# deska.net
KiCad netlist of a schematic drawn in EAGLE
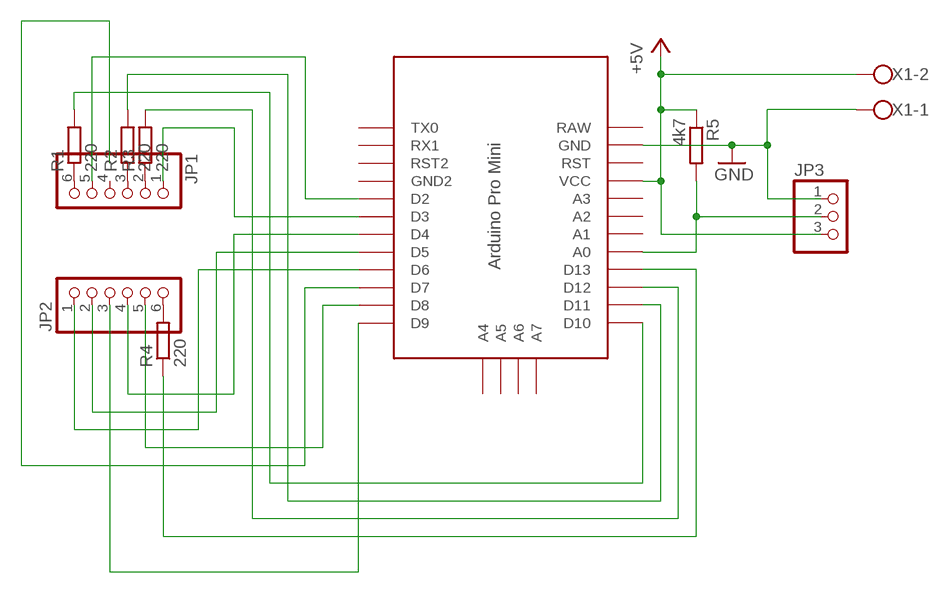
[diagram p0: schematic, sheet 1]

(export (version "E")
  (design (tool "Eeschema 10.0.6"))
  (components
    (comp (ref "JP1")
      (value "PINHD-1X6")
      (footprint "eagle-import:1X06")
      (libsource (lib "eagle-import") (part "PINHD-1X6"))
    )
    (comp (ref "JP2")
      (value "PINHD-1X6")
      (footprint "eagle-import:1X06")
      (libsource (lib "eagle-import") (part "PINHD-1X6"))
    )
    (comp (ref "JP3")
      (value "PINHD-1X3")
      (footprint "eagle-import:1X03")
      (libsource (lib "eagle-import") (part "PINHD-1X3"))
    )
    (comp (ref "R1")
      (value "220")
      (footprint "eagle-import:0204_7")
      (libsource (lib "eagle-import") (part "R-EU_0204/7"))
    )
    (comp (ref "R2")
      (value "220")
      (footprint "eagle-import:0204_7")
      (libsource (lib "eagle-import") (part "R-EU_0204/7"))
    )
    (comp (ref "R3")
      (value "220")
      (footprint "eagle-import:0204_7")
      (libsource (lib "eagle-import") (part "R-EU_0204/7"))
    )
    (comp (ref "R4")
      (value "220")
      (footprint "eagle-import:0204_7")
      (libsource (lib "eagle-import") (part "R-EU_0204/7"))
    )
    (comp (ref "R5")
      (value "4k7")
      (footprint "eagle-import:0204_7")
      (libsource (lib "eagle-import") (part "R-EU_0204/7"))
    )
    (comp (ref "U$1")
      (value "PRO-MINI")
      (footprint "eagle-import:PRO-MINI")
      (libsource (lib "eagle-import") (part "PRO-MINI"))
    )
    (comp (ref "X1")
      (value "W237-102")
      (footprint "eagle-import:W237-102")
      (fields (field (name "MPN") "237-102"))
      (libsource (lib "eagle-import") (part "W237-102"))
    )
  )
  (nets
    (net (code "1") (name "+5V") (class "Default")
      (node (ref "JP3") (pin "3") (pinfunction "3_3") (pintype "passive"))
      (node (ref "R5") (pin "1") (pinfunction "1_1") (pintype "passive"))
      (node (ref "U$1") (pin "VCC") (pinfunction "VCC_VCC") (pintype "bidirectional"))
      (node (ref "X1") (pin "2") (pinfunction "KL_2") (pintype "passive"))
    )
    (net (code "2") (name "/RAW") (class "Default")
      (node (ref "U$1") (pin "RAW") (pinfunction "RAW_RAW") (pintype "power_in"))
    )
    (net (code "3") (name "GND") (class "Default")
      (node (ref "JP3") (pin "1") (pinfunction "1_1") (pintype "passive"))
      (node (ref "U$1") (pin "GND") (pinfunction "GND_GND") (pintype "input"))
      (node (ref "X1") (pin "1") (pinfunction "KL_1") (pintype "passive"))
    )
    (net (code "4") (name "Net-(JP1-Pad1)") (class "Default")
      (node (ref "JP1") (pin "1") (pinfunction "1_1") (pintype "passive"))
      (node (ref "U$1") (pin "D3") (pinfunction "D3_D3") (pintype "bidirectional"))
    )
    (net (code "5") (name "Net-(JP1-Pad2)") (class "Default")
      (node (ref "JP1") (pin "2") (pinfunction "2_2") (pintype "passive"))
      (node (ref "R3") (pin "1") (pinfunction "1_1") (pintype "passive"))
    )
    (net (code "6") (name "Net-(JP1-Pad3)") (class "Default")
      (node (ref "JP1") (pin "3") (pinfunction "3_3") (pintype "passive"))
      (node (ref "R2") (pin "1") (pinfunction "1_1") (pintype "passive"))
    )
    (net (code "7") (name "Net-(JP1-Pad5)") (class "Default")
      (node (ref "JP1") (pin "5") (pinfunction "5_5") (pintype "passive"))
      (node (ref "U$1") (pin "D2") (pinfunction "D2_D2") (pintype "bidirectional"))
    )
    (net (code "8") (name "Net-(JP1-Pad6)") (class "Default")
      (node (ref "JP1") (pin "6") (pinfunction "6_6") (pintype "passive"))
      (node (ref "R1") (pin "1") (pinfunction "1_1") (pintype "passive"))
    )
    (net (code "9") (name "Net-(JP2-Pad1)") (class "Default")
      (node (ref "JP2") (pin "1") (pinfunction "1_1") (pintype "passive"))
      (node (ref "U$1") (pin "D6") (pinfunction "D6_D6") (pintype "bidirectional"))
    )
    (net (code "10") (name "Net-(JP2-Pad2)") (class "Default")
      (node (ref "JP2") (pin "2") (pinfunction "2_2") (pintype "passive"))
      (node (ref "U$1") (pin "D5") (pinfunction "D5_D5") (pintype "bidirectional"))
    )
    (net (code "11") (name "Net-(JP2-Pad3)") (class "Default")
      (node (ref "JP2") (pin "3") (pinfunction "3_3") (pintype "passive"))
      (node (ref "U$1") (pin "D9") (pinfunction "D9_D9") (pintype "bidirectional"))
    )
    (net (code "12") (name "Net-(JP2-Pad4)") (class "Default")
      (node (ref "JP2") (pin "4") (pinfunction "4_4") (pintype "passive"))
      (node (ref "U$1") (pin "D4") (pinfunction "D4_D4") (pintype "bidirectional"))
    )
    (net (code "13") (name "Net-(JP2-Pad5)") (class "Default")
      (node (ref "JP2") (pin "5") (pinfunction "5_5") (pintype "passive"))
      (node (ref "U$1") (pin "D8") (pinfunction "D8_D8") (pintype "bidirectional"))
    )
    (net (code "14") (name "Net-(JP2-Pad6)") (class "Default")
      (node (ref "JP2") (pin "6") (pinfunction "6_6") (pintype "passive"))
      (node (ref "R4") (pin "2") (pinfunction "2_2") (pintype "passive"))
    )
    (net (code "15") (name "Net-(JP3-Pad2)") (class "Default")
      (node (ref "JP3") (pin "2") (pinfunction "2_2") (pintype "passive"))
      (node (ref "R5") (pin "2") (pinfunction "2_2") (pintype "passive"))
      (node (ref "U$1") (pin "A0") (pinfunction "A0_A0") (pintype "bidirectional"))
    )
    (net (code "16") (name "Net-(R1-Pad2)") (class "Default")
      (node (ref "R1") (pin "2") (pinfunction "2_2") (pintype "passive"))
      (node (ref "U$1") (pin "D10") (pinfunction "D10_D10") (pintype "bidirectional"))
    )
    (net (code "17") (name "Net-(R2-Pad2)") (class "Default")
      (node (ref "R2") (pin "2") (pinfunction "2_2") (pintype "passive"))
      (node (ref "U$1") (pin "D11") (pinfunction "D11_D11") (pintype "bidirectional"))
    )
    (net (code "18") (name "Net-(R3-Pad2)") (class "Default")
      (node (ref "R3") (pin "2") (pinfunction "2_2") (pintype "passive"))
      (node (ref "U$1") (pin "D12") (pinfunction "D12_D12") (pintype "bidirectional"))
    )
    (net (code "19") (name "Net-(R4-Pad1)") (class "Default")
      (node (ref "R4") (pin "1") (pinfunction "1_1") (pintype "passive"))
      (node (ref "U$1") (pin "D13") (pinfunction "D13_D13") (pintype "bidirectional"))
    )
    (net (code "20") (name "unconnected-(JP1-Pad4)") (class "Default")
      (node (ref "JP1") (pin "4") (pinfunction "4_4") (pintype "passive"))
    )
    (net (code "21") (name "unconnected-(U$1-GND2-PadGND1)") (class "Default")
      (node (ref "U$1") (pin "GND1") (pinfunction "GND2_GND1") (pintype "bidirectional"))
    )
    (net (code "22") (name "unconnected-(U$1-PadA1)") (class "Default")
      (node (ref "U$1") (pin "A1") (pinfunction "A1_A1") (pintype "bidirectional"))
    )
    (net (code "23") (name "unconnected-(U$1-PadA2)") (class "Default")
      (node (ref "U$1") (pin "A2") (pinfunction "A2_A2") (pintype "bidirectional"))
    )
    (net (code "24") (name "unconnected-(U$1-PadA3)") (class "Default")
      (node (ref "U$1") (pin "A3") (pinfunction "A3_A3") (pintype "bidirectional"))
    )
    (net (code "25") (name "unconnected-(U$1-PadA4)") (class "Default")
      (node (ref "U$1") (pin "A4") (pinfunction "A4_A4") (pintype "bidirectional"))
    )
    (net (code "26") (name "unconnected-(U$1-PadA5)") (class "Default")
      (node (ref "U$1") (pin "A5") (pinfunction "A5_A5") (pintype "bidirectional"))
    )
    (net (code "27") (name "unconnected-(U$1-PadA6)") (class "Default")
      (node (ref "U$1") (pin "A6") (pinfunction "A6_A6") (pintype "bidirectional"))
    )
    (net (code "28") (name "unconnected-(U$1-PadA7)") (class "Default")
      (node (ref "U$1") (pin "A7") (pinfunction "A7_A7") (pintype "bidirectional"))
    )
    (net (code "29") (name "unconnected-(U$1-PadD7)") (class "Default")
      (node (ref "U$1") (pin "D7") (pinfunction "D7_D7") (pintype "bidirectional"))
    )
    (net (code "30") (name "unconnected-(U$1-PadRST)") (class "Default")
      (node (ref "U$1") (pin "RST") (pinfunction "RST_RST") (pintype "bidirectional"))
    )
    (net (code "31") (name "unconnected-(U$1-PadRX1)") (class "Default")
      (node (ref "U$1") (pin "RX1") (pinfunction "RX1_RX1") (pintype "bidirectional"))
    )
    (net (code "32") (name "unconnected-(U$1-PadTX0)") (class "Default")
      (node (ref "U$1") (pin "TX0") (pinfunction "TX0_TX0") (pintype "bidirectional"))
    )
    (net (code "33") (name "unconnected-(U$1-RST2-PadRST1)") (class "Default")
      (node (ref "U$1") (pin "RST1") (pinfunction "RST2_RST1") (pintype "bidirectional"))
    )
  )
)
